# Overview.net
KiCad netlist of a schematic drawn in Altium Designer
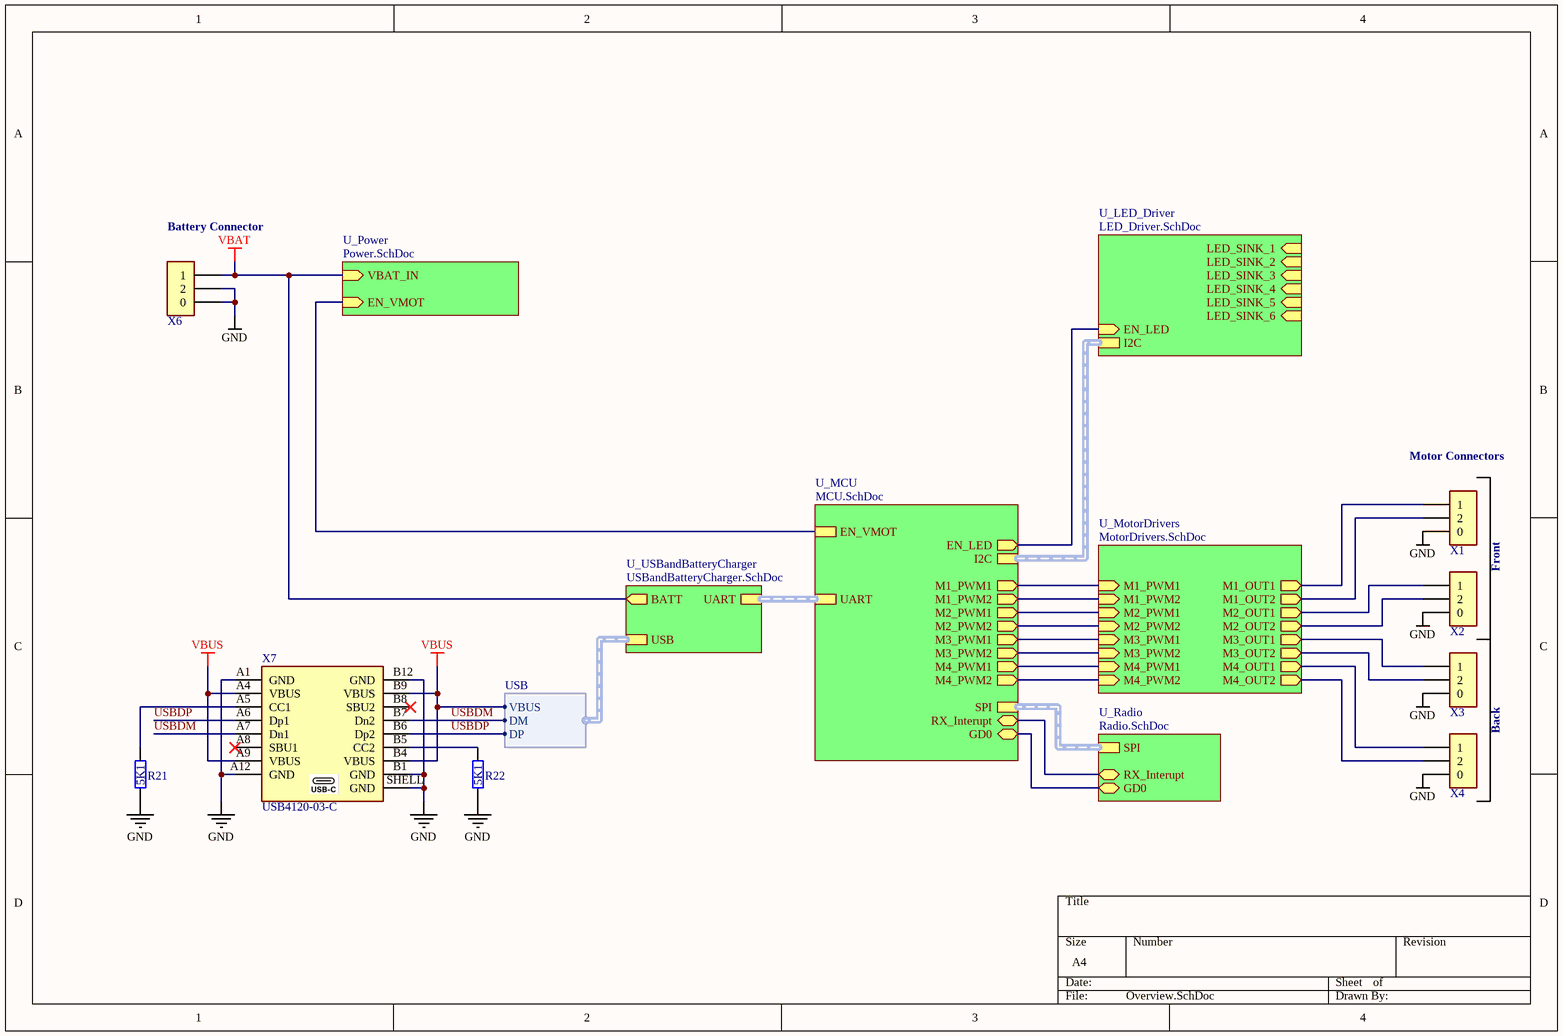
[diagram p0: Overview.SchDoc]

(export (version "E")
  (design (tool "Eeschema 10.0.6"))
  (components
    (comp (ref "R21")
      (value "5K1")
      (footprint "0603")
      (fields
        (field (name "PART NUMBER") "000053")
        (field (name "JLCPCB PART #") "C23196")
        (field (name "MANUFACTURER") "YAGEO")
      )
      (libsource (lib "TychosLibrary") (part "Resistor"))
    )
    (comp (ref "R22")
      (value "5K1")
      (footprint "0603")
      (fields
        (field (name "PART NUMBER") "000053")
        (field (name "JLCPCB PART #") "C23196")
        (field (name "MANUFACTURER") "YAGEO")
      )
      (libsource (lib "TychosLibrary") (part "Resistor"))
    )
    (comp (ref "X1")
      (value "BM02B-SRSS-TB")
      (footprint "BM02B-SRSS-TB")
      (fields (field (name "MANUFACTURER") "JST"))
      (libsource (lib "Schematic") (part "BM02B-SRSS-TB"))
    )
    (comp (ref "X2")
      (value "BM02B-SRSS-TB")
      (footprint "BM02B-SRSS-TB")
      (fields (field (name "MANUFACTURER") "JST"))
      (libsource (lib "Schematic") (part "BM02B-SRSS-TB"))
    )
    (comp (ref "X3")
      (value "BM02B-SRSS-TB")
      (footprint "BM02B-SRSS-TB")
      (fields (field (name "MANUFACTURER") "JST"))
      (libsource (lib "Schematic") (part "BM02B-SRSS-TB"))
    )
    (comp (ref "X4")
      (value "BM02B-SRSS-TB")
      (footprint "BM02B-SRSS-TB")
      (fields (field (name "MANUFACTURER") "JST"))
      (libsource (lib "Schematic") (part "BM02B-SRSS-TB"))
    )
    (comp (ref "X6")
      (value "BM02B-SRSS-TB")
      (footprint "BM02B-SRSS-TB")
      (fields (field (name "MANUFACTURER") "JST"))
      (libsource (lib "") (part "BM02B-SRSS-TB_1"))
    )
    (comp (ref "X7")
      (value "USB4120-03-C")
      (footprint "USB4120")
      (fields (field (name "MANUFACTURER") "GCT"))
      (libsource (lib "Schematic") (part "USB4120-03-C"))
    )
  )
  (nets
    (net (code "12") (name "/M1_OUT1") (class "Default")
      (node (ref "X1") (pin "1") (pinfunction "1_1") (pintype "passive"))
    )
    (net (code "13") (name "/M1_OUT2") (class "Default")
      (node (ref "X1") (pin "2") (pinfunction "2_2") (pintype "passive"))
    )
    (net (code "16") (name "/M2_OUT1") (class "Default")
      (node (ref "X2") (pin "1") (pinfunction "1_1") (pintype "passive"))
    )
    (net (code "17") (name "/M2_OUT2") (class "Default")
      (node (ref "X2") (pin "2") (pinfunction "2_2") (pintype "passive"))
    )
    (net (code "20") (name "/M3_OUT1") (class "Default")
      (node (ref "X3") (pin "1") (pinfunction "1_1") (pintype "passive"))
    )
    (net (code "21") (name "/M3_OUT2") (class "Default")
      (node (ref "X3") (pin "2") (pinfunction "2_2") (pintype "passive"))
    )
    (net (code "24") (name "/M4_OUT1") (class "Default")
      (node (ref "X4") (pin "1") (pinfunction "1_1") (pintype "passive"))
    )
    (net (code "25") (name "/M4_OUT2") (class "Default")
      (node (ref "X4") (pin "2") (pinfunction "2_2") (pintype "passive"))
    )
    (net (code "31") (name "/USBDM") (class "Default")
      (node (ref "X7") (pin "A7") (pinfunction "Dn1_A7") (pintype "passive"))
      (node (ref "X7") (pin "B7") (pinfunction "Dn2_B7") (pintype "passive"))
    )
    (net (code "32") (name "/USBDP") (class "Default")
      (node (ref "X7") (pin "A6") (pinfunction "Dp1_A6") (pintype "passive"))
      (node (ref "X7") (pin "B6") (pinfunction "Dp2_B6") (pintype "passive"))
    )
    (net (code "34") (name "GND") (class "Default")
      (node (ref "R21") (pin "1") (pinfunction "1_1") (pintype "passive"))
      (node (ref "R22") (pin "1") (pinfunction "1_1") (pintype "passive"))
      (node (ref "X1") (pin "0") (pinfunction "0_0") (pintype "passive"))
      (node (ref "X2") (pin "0") (pinfunction "0_0") (pintype "passive"))
      (node (ref "X3") (pin "0") (pinfunction "0_0") (pintype "passive"))
      (node (ref "X4") (pin "0") (pinfunction "0_0") (pintype "passive"))
      (node (ref "X6") (pin "0") (pinfunction "0_0") (pintype "passive"))
      (node (ref "X6") (pin "2") (pinfunction "2_2") (pintype "passive"))
      (node (ref "X7") (pin "A1") (pinfunction "GND_A1") (pintype "passive"))
      (node (ref "X7") (pin "A12") (pinfunction "GND_A12") (pintype "passive"))
      (node (ref "X7") (pin "B1") (pinfunction "GND_B1") (pintype "passive"))
      (node (ref "X7") (pin "B12") (pinfunction "GND_B12") (pintype "passive"))
      (node (ref "X7") (pin "SHELL") (pinfunction "GND_SHELL") (pintype "passive"))
    )
    (net (code "35") (name "Net-(X7-CC1)") (class "Default")
      (node (ref "R21") (pin "2") (pinfunction "2_2") (pintype "passive"))
      (node (ref "X7") (pin "A5") (pinfunction "CC1_A5") (pintype "passive"))
    )
    (net (code "36") (name "Net-(X7-CC2)") (class "Default")
      (node (ref "R22") (pin "2") (pinfunction "2_2") (pintype "passive"))
      (node (ref "X7") (pin "B5") (pinfunction "CC2_B5") (pintype "passive"))
    )
    (net (code "37") (name "VBAT") (class "Default")
      (node (ref "X6") (pin "1") (pinfunction "1_1") (pintype "passive"))
    )
    (net (code "38") (name "VBUS") (class "Default")
      (node (ref "X7") (pin "A4") (pinfunction "VBUS_A4") (pintype "passive"))
      (node (ref "X7") (pin "A9") (pinfunction "VBUS_A9") (pintype "passive"))
      (node (ref "X7") (pin "B4") (pinfunction "VBUS_B4") (pintype "passive"))
      (node (ref "X7") (pin "B9") (pinfunction "VBUS_B9") (pintype "passive"))
    )
    (net (code "39") (name "unconnected-(X7-SBU1-PadA8)") (class "Default")
      (node (ref "X7") (pin "A8") (pinfunction "SBU1_A8") (pintype "passive+no_connect"))
    )
    (net (code "40") (name "unconnected-(X7-SBU2-PadB8)") (class "Default")
      (node (ref "X7") (pin "B8") (pinfunction "SBU2_B8") (pintype "passive+no_connect"))
    )
  )
)
